# SCH_DRV8701_on_Boosted_Supply_2023-01-10.net
KiCad netlist of a schematic drawn in EasyEDA
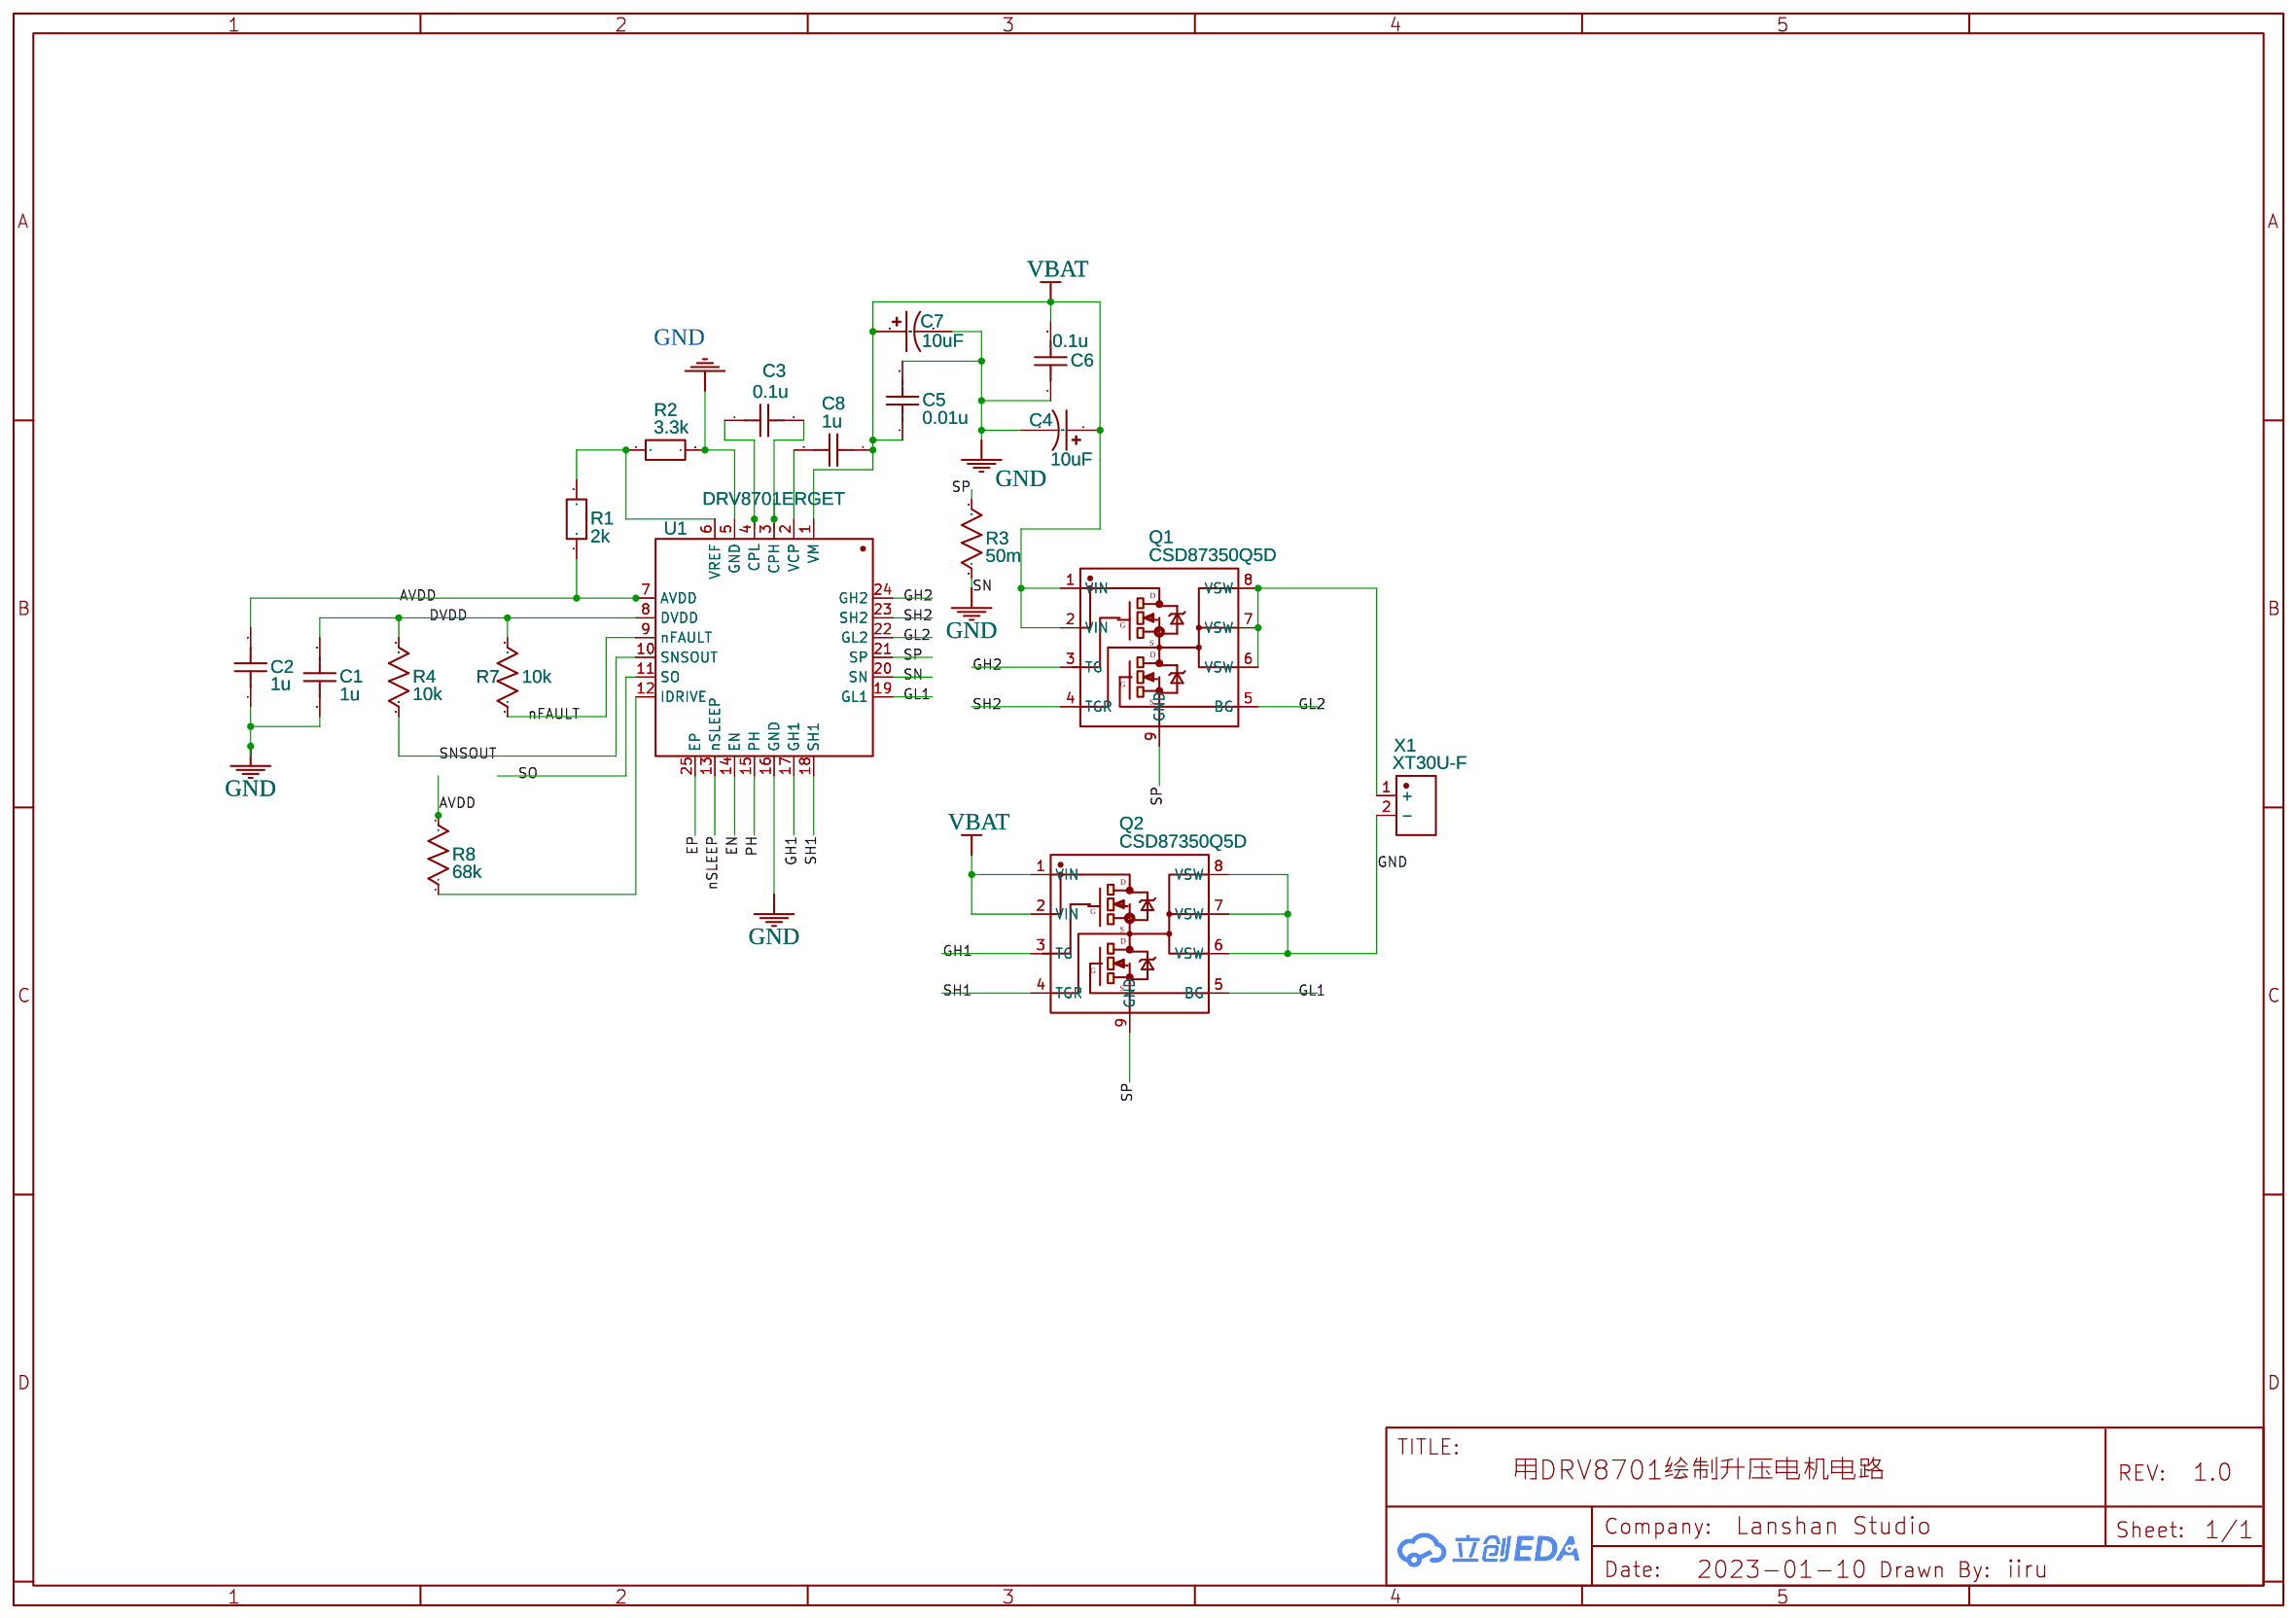
[diagram p0: schematic sheet]

(export (version "E")
  (design (tool "Eeschema 10.0.6"))
  (components
    (comp (ref "C1") (value "1u") (libsource (lib "") (part "C_0603_US")))
    (comp (ref "C2") (value "1u") (libsource (lib "") (part "C_0603_US_1")))
    (comp (ref "C3") (value "0.1u") (libsource (lib "") (part "C_0603_US_3")))
    (comp (ref "C4") (value "10uF") (libsource (lib "") (part "C_Tan_SMD_A_US_1")))
    (comp (ref "C5") (value "0.01u") (libsource (lib "") (part "C_0603_US_1")))
    (comp (ref "C6") (value "0.1u") (libsource (lib "") (part "C_0603_US_1")))
    (comp (ref "C7") (value "10uF") (libsource (lib "") (part "C_Tan_SMD_A_US")))
    (comp (ref "C8") (value "1u") (libsource (lib "") (part "C_0603_US_2")))
    (comp (ref "Q1")
      (value "CSD87350Q5D")
      (fields (field (name "BOM_Supplier Part") "C140356"))
      (libsource (lib "") (part "CSD87350Q5D"))
    )
    (comp (ref "Q2")
      (value "CSD87350Q5D")
      (fields (field (name "BOM_Supplier Part") "C140356"))
      (libsource (lib "") (part "CSD87350Q5D"))
    )
    (comp (ref "R1") (value "2k") (libsource (lib "") (part "R_0603_EU_1")))
    (comp (ref "R2") (value "3.3k") (libsource (lib "") (part "R_0603_EU")))
    (comp (ref "R3") (value "50m") (libsource (lib "") (part "R_0603_US")))
    (comp (ref "R4") (value "10k") (libsource (lib "") (part "R_0603_US")))
    (comp (ref "R7") (value "10k") (libsource (lib "") (part "R_0603_US")))
    (comp (ref "R8") (value "68k") (libsource (lib "") (part "R_0603_US")))
    (comp (ref "U1")
      (value "DRV8701ERGET")
      (fields (field (name "BOM_Supplier Part") "C132049"))
      (libsource (lib "") (part "DRV8701ERGET"))
    )
    (comp (ref "X1")
      (value "XT30U-F")
      (fields (field (name "BOM_Supplier Part") "C99102"))
      (libsource (lib "") (part "XT30U-F"))
    )
  )
  (nets
    (net (code "1") (name "/AVDD") (class "Default")
      (node (ref "C2") (pin "2") (pinfunction "2_2") (pintype "unspecified"))
      (node (ref "R1") (pin "1") (pinfunction "1_1") (pintype "unspecified"))
      (node (ref "R8") (pin "2") (pinfunction "2_2") (pintype "unspecified"))
      (node (ref "U1") (pin "7") (pinfunction "AVDD_7") (pintype "unspecified"))
    )
    (net (code "2") (name "/DVDD") (class "Default")
      (node (ref "C1") (pin "1") (pinfunction "1_1") (pintype "unspecified"))
      (node (ref "R4") (pin "2") (pinfunction "2_2") (pintype "unspecified"))
      (node (ref "R7") (pin "2") (pinfunction "2_2") (pintype "unspecified"))
      (node (ref "U1") (pin "8") (pinfunction "DVDD_8") (pintype "unspecified"))
    )
    (net (code "3") (name "/EN") (class "Default")
      (node (ref "U1") (pin "14") (pinfunction "EN_14") (pintype "unspecified"))
    )
    (net (code "4") (name "/EP") (class "Default")
      (node (ref "U1") (pin "25") (pinfunction "EP_25") (pintype "unspecified"))
    )
    (net (code "5") (name "/GH1") (class "Default")
      (node (ref "Q2") (pin "3") (pinfunction "TG_3") (pintype "unspecified"))
      (node (ref "U1") (pin "17") (pinfunction "GH1_17") (pintype "unspecified"))
    )
    (net (code "6") (name "/GH2") (class "Default")
      (node (ref "Q1") (pin "3") (pinfunction "TG_3") (pintype "unspecified"))
      (node (ref "U1") (pin "24") (pinfunction "GH2_24") (pintype "unspecified"))
    )
    (net (code "7") (name "/GL1") (class "Default")
      (node (ref "Q2") (pin "5") (pinfunction "BG_5") (pintype "unspecified"))
      (node (ref "U1") (pin "19") (pinfunction "GL1_19") (pintype "unspecified"))
    )
    (net (code "8") (name "/GL2") (class "Default")
      (node (ref "Q1") (pin "5") (pinfunction "BG_5") (pintype "unspecified"))
      (node (ref "U1") (pin "22") (pinfunction "GL2_22") (pintype "unspecified"))
    )
    (net (code "9") (name "/PH") (class "Default")
      (node (ref "U1") (pin "15") (pinfunction "PH_15") (pintype "unspecified"))
    )
    (net (code "10") (name "/SH1") (class "Default")
      (node (ref "Q2") (pin "4") (pinfunction "TGR_4") (pintype "unspecified"))
      (node (ref "U1") (pin "18") (pinfunction "SH1_18") (pintype "unspecified"))
    )
    (net (code "11") (name "/SH2") (class "Default")
      (node (ref "Q1") (pin "4") (pinfunction "TGR_4") (pintype "unspecified"))
      (node (ref "U1") (pin "23") (pinfunction "SH2_23") (pintype "unspecified"))
    )
    (net (code "12") (name "/SNSOUT") (class "Default")
      (node (ref "R4") (pin "1") (pinfunction "1_1") (pintype "unspecified"))
      (node (ref "U1") (pin "10") (pinfunction "SNSOUT_10") (pintype "unspecified"))
    )
    (net (code "13") (name "/SO") (class "Default")
      (node (ref "U1") (pin "11") (pinfunction "SO_11") (pintype "unspecified"))
    )
    (net (code "14") (name "/SP") (class "Default")
      (node (ref "Q1") (pin "9") (pinfunction "GND_9") (pintype "unspecified"))
      (node (ref "Q2") (pin "9") (pinfunction "GND_9") (pintype "unspecified"))
      (node (ref "R3") (pin "2") (pinfunction "2_2") (pintype "unspecified"))
      (node (ref "U1") (pin "21") (pinfunction "SP_21") (pintype "unspecified"))
    )
    (net (code "15") (name "/nFAULT") (class "Default")
      (node (ref "R7") (pin "1") (pinfunction "1_1") (pintype "unspecified"))
      (node (ref "U1") (pin "9") (pinfunction "nFAULT_9") (pintype "unspecified"))
    )
    (net (code "16") (name "/nSLEEP") (class "Default")
      (node (ref "U1") (pin "13") (pinfunction "nSLEEP_13") (pintype "unspecified"))
    )
    (net (code "17") (name "GND") (class "Default")
      (node (ref "C1") (pin "2") (pinfunction "2_2") (pintype "unspecified"))
      (node (ref "C2") (pin "1") (pinfunction "1_1") (pintype "unspecified"))
      (node (ref "C4") (pin "2") (pinfunction "2_2") (pintype "unspecified"))
      (node (ref "C5") (pin "2") (pinfunction "2_2") (pintype "unspecified"))
      (node (ref "C6") (pin "1") (pinfunction "1_1") (pintype "unspecified"))
      (node (ref "C7") (pin "2") (pinfunction "2_2") (pintype "unspecified"))
      (node (ref "Q2") (pin "6") (pinfunction "VSW_6") (pintype "unspecified"))
      (node (ref "Q2") (pin "7") (pinfunction "VSW_7") (pintype "unspecified"))
      (node (ref "Q2") (pin "8") (pinfunction "VSW_8") (pintype "unspecified"))
      (node (ref "R2") (pin "2") (pinfunction "2_2") (pintype "unspecified"))
      (node (ref "R3") (pin "1") (pinfunction "1_1") (pintype "unspecified"))
      (node (ref "U1") (pin "16") (pinfunction "GND_16") (pintype "unspecified"))
      (node (ref "U1") (pin "20") (pinfunction "SN_20") (pintype "unspecified"))
      (node (ref "U1") (pin "5") (pinfunction "GND_5") (pintype "unspecified"))
      (node (ref "X1") (pin "2") (pinfunction "-_2") (pintype "unspecified"))
    )
    (net (code "18") (name "Net-(U1-CPH)") (class "Default")
      (node (ref "C3") (pin "2") (pinfunction "2_2") (pintype "unspecified"))
      (node (ref "U1") (pin "3") (pinfunction "CPH_3") (pintype "unspecified"))
    )
    (net (code "19") (name "Net-(U1-CPL)") (class "Default")
      (node (ref "C3") (pin "1") (pinfunction "1_1") (pintype "unspecified"))
      (node (ref "U1") (pin "4") (pinfunction "CPL_4") (pintype "unspecified"))
    )
    (net (code "20") (name "Net-(U1-IDRIVE)") (class "Default")
      (node (ref "R8") (pin "1") (pinfunction "1_1") (pintype "unspecified"))
      (node (ref "U1") (pin "12") (pinfunction "IDRIVE_12") (pintype "unspecified"))
    )
    (net (code "21") (name "Net-(U1-VCP)") (class "Default")
      (node (ref "C8") (pin "2") (pinfunction "2_2") (pintype "unspecified"))
      (node (ref "U1") (pin "2") (pinfunction "VCP_2") (pintype "unspecified"))
    )
    (net (code "22") (name "Net-(U1-VREF)") (class "Default")
      (node (ref "R1") (pin "2") (pinfunction "2_2") (pintype "unspecified"))
      (node (ref "R2") (pin "1") (pinfunction "1_1") (pintype "unspecified"))
      (node (ref "U1") (pin "6") (pinfunction "VREF_6") (pintype "unspecified"))
    )
    (net (code "23") (name "Net-(X1-+)") (class "Default")
      (node (ref "Q1") (pin "6") (pinfunction "VSW_6") (pintype "unspecified"))
      (node (ref "Q1") (pin "7") (pinfunction "VSW_7") (pintype "unspecified"))
      (node (ref "Q1") (pin "8") (pinfunction "VSW_8") (pintype "unspecified"))
      (node (ref "X1") (pin "1") (pinfunction "+_1") (pintype "unspecified"))
    )
    (net (code "24") (name "VBAT") (class "Default")
      (node (ref "C4") (pin "1") (pinfunction "1_1") (pintype "unspecified"))
      (node (ref "C5") (pin "1") (pinfunction "1_1") (pintype "unspecified"))
      (node (ref "C6") (pin "2") (pinfunction "2_2") (pintype "unspecified"))
      (node (ref "C7") (pin "1") (pinfunction "1_1") (pintype "unspecified"))
      (node (ref "C8") (pin "1") (pinfunction "1_1") (pintype "unspecified"))
      (node (ref "Q1") (pin "1") (pinfunction "VIN_1") (pintype "unspecified"))
      (node (ref "Q1") (pin "2") (pinfunction "VIN_2") (pintype "unspecified"))
      (node (ref "Q2") (pin "1") (pinfunction "VIN_1") (pintype "unspecified"))
      (node (ref "Q2") (pin "2") (pinfunction "VIN_2") (pintype "unspecified"))
      (node (ref "U1") (pin "1") (pinfunction "VM_1") (pintype "unspecified"))
    )
  )
)
